# mixer_1GHz_rat_race_discreto.net
KiCad netlist of a schematic drawn in Altium Designer
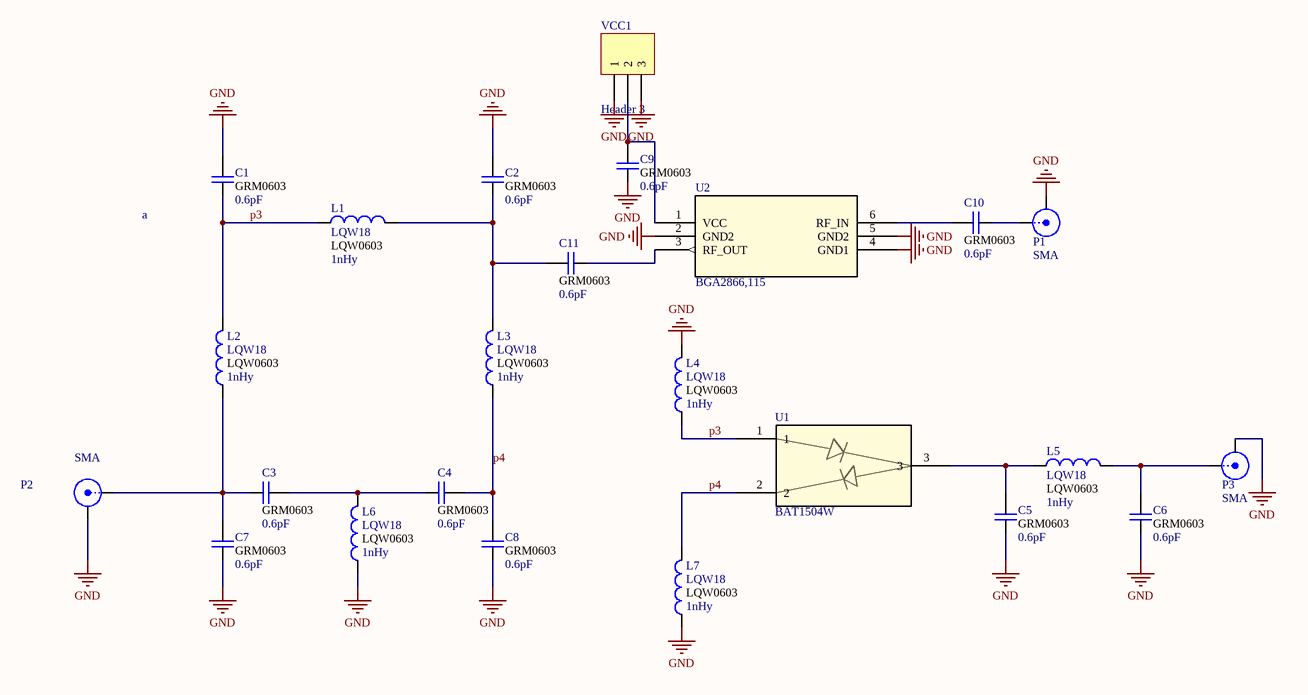
[diagram p0: mixer_1GHz_rat_race_discreto.SchDoc]

(export (version "E")
  (design (tool "Eeschema 10.0.6"))
  (components
    (comp (ref "C1")
      (value "0.6pF")
      (footprint "GRM0603")
      (description "Capacitor GRM18 0603")
      (fields (field (name "Comment") "Cap 0603") (field (name "PUBLISHER") "Altium Limited"))
      (libsource (lib "Radar_RF_EAIII") (part "Cap"))
    )
    (comp (ref "C2")
      (value "0.6pF")
      (footprint "GRM0603")
      (description "Capacitor GRM18 0603")
      (fields (field (name "Comment") "Cap 0603") (field (name "PUBLISHER") "Altium Limited"))
      (libsource (lib "Radar_RF_EAIII") (part "Cap"))
    )
    (comp (ref "C3")
      (value "0.6pF")
      (footprint "GRM0603")
      (description "Capacitor GRM18 0603")
      (fields (field (name "Comment") "Cap 0603") (field (name "PUBLISHER") "Altium Limited"))
      (libsource (lib "Radar_RF_EAIII") (part "Cap"))
    )
    (comp (ref "C4")
      (value "0.6pF")
      (footprint "GRM0603")
      (description "Capacitor GRM18 0603")
      (fields (field (name "Comment") "Cap 0603") (field (name "PUBLISHER") "Altium Limited"))
      (libsource (lib "Radar_RF_EAIII") (part "Cap"))
    )
    (comp (ref "C5")
      (value "0.6pF")
      (footprint "GRM0603")
      (description "Capacitor GRM18 0603")
      (fields (field (name "Comment") "Cap 0603") (field (name "PUBLISHER") "Altium Limited"))
      (libsource (lib "Radar_RF_EAIII") (part "Cap"))
    )
    (comp (ref "C6")
      (value "0.6pF")
      (footprint "GRM0603")
      (description "Capacitor GRM18 0603")
      (fields (field (name "Comment") "Cap 0603") (field (name "PUBLISHER") "Altium Limited"))
      (libsource (lib "Radar_RF_EAIII") (part "Cap"))
    )
    (comp (ref "C7")
      (value "0.6pF")
      (footprint "GRM0603")
      (description "Capacitor GRM18 0603")
      (fields (field (name "Comment") "Cap 0603") (field (name "PUBLISHER") "Altium Limited"))
      (libsource (lib "Radar_RF_EAIII") (part "Cap"))
    )
    (comp (ref "C8")
      (value "0.6pF")
      (footprint "GRM0603")
      (description "Capacitor GRM18 0603")
      (fields (field (name "Comment") "Cap 0603") (field (name "PUBLISHER") "Altium Limited"))
      (libsource (lib "Radar_RF_EAIII") (part "Cap"))
    )
    (comp (ref "C9")
      (value "0.6pF")
      (footprint "GRM0603")
      (description "Capacitor GRM18 0603")
      (fields (field (name "Comment") "Cap 0603") (field (name "PUBLISHER") "Altium Limited"))
      (libsource (lib "Radar_RF_EAIII") (part "Cap"))
    )
    (comp (ref "C10")
      (value "0.6pF")
      (footprint "GRM0603")
      (description "Capacitor GRM18 0603")
      (fields (field (name "Comment") "Cap 0603") (field (name "PUBLISHER") "Altium Limited"))
      (libsource (lib "Radar_RF_EAIII") (part "Cap"))
    )
    (comp (ref "C11")
      (value "0.6pF")
      (footprint "GRM0603")
      (description "Capacitor GRM18 0603")
      (fields (field (name "Comment") "Cap 0603") (field (name "PUBLISHER") "Altium Limited"))
      (libsource (lib "Radar_RF_EAIII") (part "Cap"))
    )
    (comp (ref "L1")
      (value "LQW18")
      (footprint "INDC1608X100N")
      (description "Ind RF Chip Wirewound 18nH 5% 100MHz 40Q-Factor 550mA 0603 Paper T/R")
      (fields
        (field (name "MP") "LQW18AN18NJ00D")
        (field (name "PARAMETER 1") "LQW0603")
        (field (name "ALTIUM_VALUE") "1nHy")
      )
      (libsource (lib "Radar_RF_EAIII") (part "LQW18"))
    )
    (comp (ref "L2")
      (value "LQW18")
      (footprint "INDC1608X100N")
      (description "Ind RF Chip Wirewound 18nH 5% 100MHz 40Q-Factor 550mA 0603 Paper T/R")
      (fields
        (field (name "MP") "LQW18AN18NJ00D")
        (field (name "PARAMETER 1") "LQW0603")
        (field (name "ALTIUM_VALUE") "1nHy")
      )
      (libsource (lib "Radar_RF_EAIII") (part "LQW18"))
    )
    (comp (ref "L3")
      (value "LQW18")
      (footprint "INDC1608X100N")
      (description "Ind RF Chip Wirewound 18nH 5% 100MHz 40Q-Factor 550mA 0603 Paper T/R")
      (fields
        (field (name "MP") "LQW18AN18NJ00D")
        (field (name "PARAMETER 1") "LQW0603")
        (field (name "ALTIUM_VALUE") "1nHy")
      )
      (libsource (lib "Radar_RF_EAIII") (part "LQW18"))
    )
    (comp (ref "L4")
      (value "LQW18")
      (footprint "INDC1608X100N")
      (description "Ind RF Chip Wirewound 18nH 5% 100MHz 40Q-Factor 550mA 0603 Paper T/R")
      (fields
        (field (name "MP") "LQW18AN18NJ00D")
        (field (name "PARAMETER 1") "LQW0603")
        (field (name "ALTIUM_VALUE") "1nHy")
      )
      (libsource (lib "Radar_RF_EAIII") (part "LQW18"))
    )
    (comp (ref "L5")
      (value "LQW18")
      (footprint "INDC1608X100N")
      (description "Ind RF Chip Wirewound 18nH 5% 100MHz 40Q-Factor 550mA 0603 Paper T/R")
      (fields
        (field (name "MP") "LQW18AN18NJ00D")
        (field (name "PARAMETER 1") "LQW0603")
        (field (name "ALTIUM_VALUE") "1nHy")
      )
      (libsource (lib "Radar_RF_EAIII") (part "LQW18"))
    )
    (comp (ref "L6")
      (value "LQW18")
      (footprint "INDC1608X100N")
      (description "Ind RF Chip Wirewound 18nH 5% 100MHz 40Q-Factor 550mA 0603 Paper T/R")
      (fields
        (field (name "MP") "LQW18AN18NJ00D")
        (field (name "PARAMETER 1") "LQW0603")
        (field (name "ALTIUM_VALUE") "1nHy")
      )
      (libsource (lib "Radar_RF_EAIII") (part "LQW18"))
    )
    (comp (ref "L7")
      (value "LQW18")
      (footprint "INDC1608X100N")
      (description "Ind RF Chip Wirewound 18nH 5% 100MHz 40Q-Factor 550mA 0603 Paper T/R")
      (fields
        (field (name "MP") "LQW18AN18NJ00D")
        (field (name "PARAMETER 1") "LQW0603")
        (field (name "ALTIUM_VALUE") "1nHy")
      )
      (libsource (lib "Radar_RF_EAIII") (part "LQW18"))
    )
    (comp (ref "P1")
      (value "SMA")
      (footprint "SMA-142-0701-851_V2")
      (description "SMB Straight Connector")
      (fields (field (name "PUBLISHER") "Altium Limited"))
      (libsource (lib "PCB_Project") (part "SMB"))
    )
    (comp (ref "P2")
      (value "SMA")
      (footprint "SMA-142-0701-851_V2")
      (description "SMB Straight Connector")
      (fields (field (name "PUBLISHER") "Altium Limited"))
      (libsource (lib "PCB_Project") (part "SMB"))
    )
    (comp (ref "P3")
      (value "SMA")
      (footprint "SMA-142-0701-851_V2")
      (description "SMB Straight Connector")
      (fields (field (name "PUBLISHER") "Altium Limited"))
      (libsource (lib "PCB_Project") (part "SMB"))
    )
    (comp (ref "U1")
      (value "BAT1504W")
      (footprint "SOT_327XTSA1_INF")
      (description "Diodo")
      (libsource (lib "Radar_RF_EAIII") (part "BAT1504W"))
    )
    (comp (ref "U2")
      (value "BGA2866,115")
      (footprint "SOT363_NXP")
      (description "No Description Available")
      (libsource (lib "Radar_RF_EAIII") (part "BGA2866,115"))
    )
    (comp (ref "VCC1")
      (value "Header 3")
      (footprint "HDR1X3")
      (description "Header, 3-Pin")
      (fields (field (name "PUBLISHER") "Altium Limited"))
      (libsource (lib "Miscellaneous Connectors") (part "Header 3"))
    )
  )
  (nets
    (net (code "1") (name "/p3") (class "Default")
      (node (ref "C1") (pin "1") (pinfunction "1_1") (pintype "passive"))
      (node (ref "L1") (pin "1") (pinfunction "1_1") (pintype "passive"))
      (node (ref "L2") (pin "2") (pinfunction "2_2") (pintype "passive"))
      (node (ref "L4") (pin "1") (pinfunction "1_1") (pintype "passive"))
      (node (ref "U1") (pin "1") (pinfunction "1_1") (pintype "passive"))
    )
    (net (code "2") (name "/p4") (class "Default")
      (node (ref "C4") (pin "2") (pinfunction "2_2") (pintype "passive"))
      (node (ref "C8") (pin "2") (pinfunction "2_2") (pintype "passive"))
      (node (ref "L3") (pin "1") (pinfunction "1_1") (pintype "passive"))
      (node (ref "L7") (pin "2") (pinfunction "2_2") (pintype "passive"))
      (node (ref "U1") (pin "2") (pinfunction "2_2") (pintype "passive"))
    )
    (net (code "3") (name "GND") (class "Default")
      (node (ref "C1") (pin "2") (pinfunction "2_2") (pintype "passive"))
      (node (ref "C2") (pin "2") (pinfunction "2_2") (pintype "passive"))
      (node (ref "C5") (pin "1") (pinfunction "1_1") (pintype "passive"))
      (node (ref "C6") (pin "1") (pinfunction "1_1") (pintype "passive"))
      (node (ref "C7") (pin "1") (pinfunction "1_1") (pintype "passive"))
      (node (ref "C8") (pin "1") (pinfunction "1_1") (pintype "passive"))
      (node (ref "C9") (pin "1") (pinfunction "1_1") (pintype "passive"))
      (node (ref "L4") (pin "2") (pinfunction "2_2") (pintype "passive"))
      (node (ref "L6") (pin "1") (pinfunction "1_1") (pintype "passive"))
      (node (ref "L7") (pin "1") (pinfunction "1_1") (pintype "passive"))
      (node (ref "P1") (pin "2") (pinfunction "Y_2") (pintype "passive"))
      (node (ref "P2") (pin "2") (pinfunction "Y_2") (pintype "passive"))
      (node (ref "P3") (pin "2") (pinfunction "Y_2") (pintype "passive"))
      (node (ref "U2") (pin "2") (pinfunction "GND2_2") (pintype "power_in"))
      (node (ref "U2") (pin "4") (pinfunction "GND1_4") (pintype "power_in"))
      (node (ref "U2") (pin "5") (pinfunction "GND2_5") (pintype "power_in"))
      (node (ref "VCC1") (pin "1") (pinfunction "1_1") (pintype "passive"))
      (node (ref "VCC1") (pin "3") (pinfunction "3_3") (pintype "passive"))
    )
    (net (code "4") (name "Net-(C3-Pad2)") (class "Default")
      (node (ref "C3") (pin "2") (pinfunction "2_2") (pintype "passive"))
      (node (ref "C4") (pin "1") (pinfunction "1_1") (pintype "passive"))
      (node (ref "L6") (pin "2") (pinfunction "2_2") (pintype "passive"))
    )
    (net (code "5") (name "Net-(C5-Pad2)") (class "Default")
      (node (ref "C5") (pin "2") (pinfunction "2_2") (pintype "passive"))
      (node (ref "L5") (pin "1") (pinfunction "1_1") (pintype "passive"))
      (node (ref "U1") (pin "3") (pinfunction "3_3") (pintype "passive"))
    )
    (net (code "6") (name "Net-(C11-Pad2)") (class "Default")
      (node (ref "C11") (pin "2") (pinfunction "2_2") (pintype "passive"))
      (node (ref "C2") (pin "1") (pinfunction "1_1") (pintype "passive"))
      (node (ref "L1") (pin "2") (pinfunction "2_2") (pintype "passive"))
      (node (ref "L3") (pin "2") (pinfunction "2_2") (pintype "passive"))
    )
    (net (code "7") (name "Net-(P1-X)") (class "Default")
      (node (ref "C10") (pin "1") (pinfunction "1_1") (pintype "passive"))
      (node (ref "P1") (pin "1") (pinfunction "X_1") (pintype "passive"))
    )
    (net (code "8") (name "Net-(P2-X)") (class "Default")
      (node (ref "C3") (pin "1") (pinfunction "1_1") (pintype "passive"))
      (node (ref "C7") (pin "2") (pinfunction "2_2") (pintype "passive"))
      (node (ref "L2") (pin "1") (pinfunction "1_1") (pintype "passive"))
      (node (ref "P2") (pin "1") (pinfunction "X_1") (pintype "passive"))
    )
    (net (code "9") (name "Net-(P3-X)") (class "Default")
      (node (ref "C6") (pin "2") (pinfunction "2_2") (pintype "passive"))
      (node (ref "L5") (pin "2") (pinfunction "2_2") (pintype "passive"))
      (node (ref "P3") (pin "1") (pinfunction "X_1") (pintype "passive"))
    )
    (net (code "10") (name "Net-(U2-RF_IN)") (class "Default")
      (node (ref "C10") (pin "2") (pinfunction "2_2") (pintype "passive"))
      (node (ref "U2") (pin "6") (pinfunction "RF_IN_6") (pintype "passive"))
    )
    (net (code "11") (name "Net-(U2-RF_OUT)") (class "Default")
      (node (ref "C11") (pin "1") (pinfunction "1_1") (pintype "passive"))
      (node (ref "U2") (pin "3") (pinfunction "RF_OUT_3") (pintype "output"))
    )
    (net (code "12") (name "Net-(U2-VCC)") (class "Default")
      (node (ref "C9") (pin "2") (pinfunction "2_2") (pintype "passive"))
      (node (ref "U2") (pin "1") (pinfunction "VCC_1") (pintype "power_in"))
      (node (ref "VCC1") (pin "2") (pinfunction "2_2") (pintype "passive"))
    )
  )
)
